# burnwire.net
KiCad netlist of a schematic drawn in Altium Designer
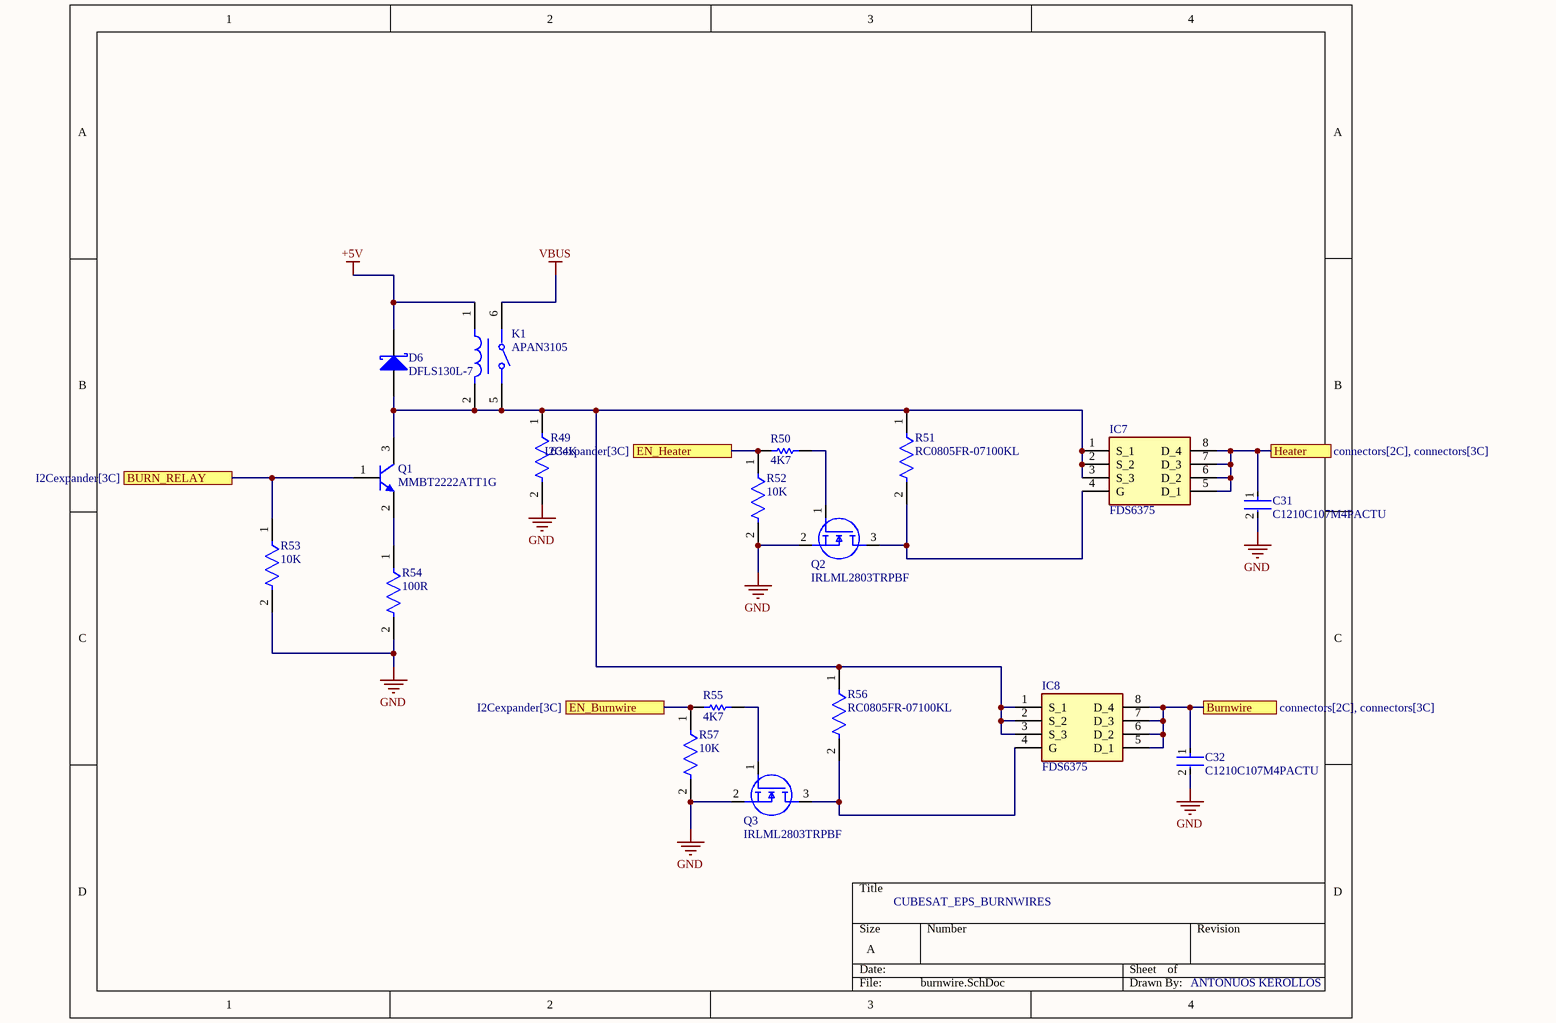
[diagram p0: burnwire.SchDoc]

(export (version "E")
  (design (tool "Eeschema 10.0.6"))
  (components
    (comp (ref "C31")
      (value "C1210C107M4PACTU")
      (footprint "FP-C1210C-FS-MFG")
      (description "CAP CER 100UF 16V X5R 1210")
      (fields (field (name "TOLERANCE") "20%"))
      (libsource (lib "Altium Content Vault") (part "02cd4be3c70576c341d710602a673aa"))
    )
    (comp (ref "C32")
      (value "C1210C107M4PACTU")
      (footprint "FP-C1210C-FS-MFG")
      (description "CAP CER 100UF 16V X5R 1210")
      (fields (field (name "TOLERANCE") "20%"))
      (libsource (lib "Altium Content Vault") (part "02cd4be3c70576c341d710602a673aa"))
    )
    (comp (ref "D6")
      (value "DFLS130L-7")
      (footprint "DIOD-POWERDI123-2_A_V")
      (description "Schottky Barrier Rectifier, 30 V, 1 A, -40 to 125 degC, 2-Pin SMD, RoHS, Tape and Reel")
      (fields (field (name "MANUFACTURER") "Diodes Inc"))
      (libsource (lib "Altium Content Vault") (part "DSKY-AK-2"))
    )
    (comp (ref "IC7")
      (value "FDS6375")
      (footprint "SamacSys:SOIC127P600X175-8N")
      (description "Integrated Circuit")
      (fields (field (name "MOUSER PART NUMBER") "512-FDS6375"))
      (libsource (lib "*") (part "FDS6375"))
    )
    (comp (ref "IC8")
      (value "FDS6375")
      (footprint "SamacSys:SOIC127P600X175-8N")
      (description "Integrated Circuit")
      (fields (field (name "MOUSER PART NUMBER") "512-FDS6375"))
      (libsource (lib "*") (part "FDS6375"))
    )
    (comp (ref "K1")
      (value "APAN3105")
      (footprint "FP-APAN3105-MFG")
      (description "RELAY GENERAL PURPOSE SPST 5A 5V")
      (libsource (lib "Altium Content Vault") (part "fce70d0d91a7d3418c43728939eaaf2"))
    )
    (comp (ref "Q1")
      (value "MMBT2222ATT1G")
      (footprint "ONSC-SC-75-3-463-01_V")
      (description "General Purpose Transistor, NPN Silicon, 3-Pin SC-75, Pb-Free, Tape and Reel")
      (fields (field (name "MANUFACTURER") "On Semiconductor"))
      (libsource (lib "Altium Content Vault") (part "ONSC-NPN-B1E2C3-3"))
    )
    (comp (ref "Q2")
      (value "IRLML2803TRPBF")
      (footprint "SamacSys:SOT95P237X112-3N")
      (description "MOSFET (N-Channel)")
      (fields (field (name "MOUSER PART NUMBER") "942-IRLML2803TRPBF"))
      (libsource (lib "*") (part "IRLML2803TRPBF"))
    )
    (comp (ref "Q3")
      (value "IRLML2803TRPBF")
      (footprint "SamacSys:SOT95P237X112-3N")
      (description "MOSFET (N-Channel)")
      (fields (field (name "MOUSER PART NUMBER") "942-IRLML2803TRPBF"))
      (libsource (lib "*") (part "IRLML2803TRPBF"))
    )
    (comp (ref "R49")
      (value "634K")
      (footprint "FP-CRCW0805-e3-IPC_A")
      (description "RES Thick Film, 634kΩ, 1%, 0.125W, 100ppm/°C, 0805")
      (fields (field (name "TOLERANCE") "1%"))
      (libsource (lib "Altium Content Vault") (part "1029c3af85768c4190bb7ad29bc67b5"))
    )
    (comp (ref "R50")
      (value "4K7")
      (footprint "YAGO-RC0805_M")
      (fields
        (field (name "TOLERANCE") "+/- 1%")
        (field (name "PARTNUMBER") "RC0805FR-074K7L")
        (field (name "POWER") "0.125 W")
      )
      (libsource (lib "Altium Content Vault") (part "YAGO-RES-2"))
    )
    (comp (ref "R51")
      (value "RC0805FR-07100KL")
      (footprint "FP-RC0805-0_6-IPC_C")
      (description "RES 100K OHM 1% 1/8W 0805")
      (fields (field (name "TOLERANCE") "1%"))
      (libsource (lib "Altium Content Vault") (part "1029c3af85768c4190bb7ad29bc67b5"))
    )
    (comp (ref "R52")
      (value "10K")
      (footprint "FP-CRCW0805-e3-IPC_A")
      (description "RES Thick Film, 10kΩ, 1%, 0.125W, 100ppm/°C, 0805")
      (fields (field (name "TOLERANCE") "1%"))
      (libsource (lib "Altium Content Vault") (part "1029c3af85768c4190bb7ad29bc67b5"))
    )
    (comp (ref "R53")
      (value "10K")
      (footprint "FP-CRCW0805-e3-IPC_A")
      (description "RES Thick Film, 10kΩ, 1%, 0.125W, 100ppm/°C, 0805")
      (fields (field (name "TOLERANCE") "1%"))
      (libsource (lib "Altium Content Vault") (part "1029c3af85768c4190bb7ad29bc67b5"))
    )
    (comp (ref "R54")
      (value "100R")
      (footprint "FP-RC0603-0_55-MFG")
      (fields (field (name "TOLERANCE") "1%"))
      (libsource (lib "Altium Content Vault") (part "1029c3af85768c4190bb7ad29bc67b5"))
    )
    (comp (ref "R55")
      (value "4K7")
      (footprint "YAGO-RC0805_M")
      (fields
        (field (name "TOLERANCE") "+/- 1%")
        (field (name "PARTNUMBER") "RC0805FR-074K7L")
        (field (name "POWER") "0.125 W")
      )
      (libsource (lib "Altium Content Vault") (part "YAGO-RES-2"))
    )
    (comp (ref "R56")
      (value "RC0805FR-07100KL")
      (footprint "FP-RC0805-0_6-IPC_C")
      (description "RES 100K OHM 1% 1/8W 0805")
      (fields (field (name "TOLERANCE") "1%"))
      (libsource (lib "Altium Content Vault") (part "1029c3af85768c4190bb7ad29bc67b5"))
    )
    (comp (ref "R57")
      (value "10K")
      (footprint "FP-CRCW0805-e3-IPC_A")
      (description "RES Thick Film, 10kΩ, 1%, 0.125W, 100ppm/°C, 0805")
      (fields (field (name "TOLERANCE") "1%"))
      (libsource (lib "Altium Content Vault") (part "1029c3af85768c4190bb7ad29bc67b5"))
    )
  )
  (nets
    (net (code "1") (name "+5V") (class "Default")
      (node (ref "D6") (pin "2") (pinfunction "K_2") (pintype "passive"))
      (node (ref "K1") (pin "1") (pinfunction "1_1") (pintype "passive"))
    )
    (net (code "2") (name "/BURN_RELAY") (class "Default")
      (node (ref "Q1") (pin "1") (pinfunction "B_1") (pintype "passive"))
      (node (ref "R53") (pin "1") (pinfunction "1_1") (pintype "passive"))
    )
    (net (code "3") (name "/Burnwire") (class "Default")
      (node (ref "C32") (pin "1") (pinfunction "1_1") (pintype "passive"))
      (node (ref "IC8") (pin "5") (pinfunction "D_1_5") (pintype "passive"))
      (node (ref "IC8") (pin "6") (pinfunction "D_2_6") (pintype "passive"))
      (node (ref "IC8") (pin "7") (pinfunction "D_3_7") (pintype "passive"))
      (node (ref "IC8") (pin "8") (pinfunction "D_4_8") (pintype "passive"))
    )
    (net (code "4") (name "/EN_Burnwire") (class "Default")
      (node (ref "R55") (pin "1") (pinfunction "1_1") (pintype "passive"))
      (node (ref "R57") (pin "1") (pinfunction "1_1") (pintype "passive"))
    )
    (net (code "5") (name "/EN_Heater") (class "Default")
      (node (ref "R50") (pin "1") (pinfunction "1_1") (pintype "passive"))
      (node (ref "R52") (pin "1") (pinfunction "1_1") (pintype "passive"))
    )
    (net (code "6") (name "/Heater") (class "Default")
      (node (ref "C31") (pin "1") (pinfunction "1_1") (pintype "passive"))
      (node (ref "IC7") (pin "5") (pinfunction "D_1_5") (pintype "passive"))
      (node (ref "IC7") (pin "6") (pinfunction "D_2_6") (pintype "passive"))
      (node (ref "IC7") (pin "7") (pinfunction "D_3_7") (pintype "passive"))
      (node (ref "IC7") (pin "8") (pinfunction "D_4_8") (pintype "passive"))
    )
    (net (code "7") (name "GND") (class "Default")
      (node (ref "C31") (pin "2") (pinfunction "2_2") (pintype "passive"))
      (node (ref "C32") (pin "2") (pinfunction "2_2") (pintype "passive"))
      (node (ref "Q2") (pin "2") (pinfunction "S_2") (pintype "passive"))
      (node (ref "Q3") (pin "2") (pinfunction "S_2") (pintype "passive"))
      (node (ref "R49") (pin "2") (pinfunction "2_2") (pintype "passive"))
      (node (ref "R52") (pin "2") (pinfunction "2_2") (pintype "passive"))
      (node (ref "R53") (pin "2") (pinfunction "2_2") (pintype "passive"))
      (node (ref "R54") (pin "2") (pinfunction "2_2") (pintype "passive"))
      (node (ref "R57") (pin "2") (pinfunction "2_2") (pintype "passive"))
    )
    (net (code "8") (name "Net-(D6-A)") (class "Default")
      (node (ref "D6") (pin "1") (pinfunction "A_1") (pintype "passive"))
      (node (ref "IC7") (pin "1") (pinfunction "S_1_1") (pintype "passive"))
      (node (ref "IC7") (pin "2") (pinfunction "S_2_2") (pintype "passive"))
      (node (ref "IC7") (pin "3") (pinfunction "S_3_3") (pintype "passive"))
      (node (ref "IC8") (pin "1") (pinfunction "S_1_1") (pintype "passive"))
      (node (ref "IC8") (pin "2") (pinfunction "S_2_2") (pintype "passive"))
      (node (ref "IC8") (pin "3") (pinfunction "S_3_3") (pintype "passive"))
      (node (ref "K1") (pin "2") (pinfunction "2_2") (pintype "passive"))
      (node (ref "K1") (pin "5") (pinfunction "NO_5") (pintype "passive"))
      (node (ref "Q1") (pin "3") (pinfunction "C_3") (pintype "passive"))
      (node (ref "R49") (pin "1") (pinfunction "1_1") (pintype "passive"))
      (node (ref "R51") (pin "1") (pinfunction "1_1") (pintype "passive"))
      (node (ref "R56") (pin "1") (pinfunction "1_1") (pintype "passive"))
    )
    (net (code "9") (name "Net-(IC7-G)") (class "Default")
      (node (ref "IC7") (pin "4") (pinfunction "G_4") (pintype "passive"))
      (node (ref "Q2") (pin "3") (pinfunction "D_3") (pintype "passive"))
      (node (ref "R51") (pin "2") (pinfunction "2_2") (pintype "passive"))
    )
    (net (code "10") (name "Net-(IC8-G)") (class "Default")
      (node (ref "IC8") (pin "4") (pinfunction "G_4") (pintype "passive"))
      (node (ref "Q3") (pin "3") (pinfunction "D_3") (pintype "passive"))
      (node (ref "R56") (pin "2") (pinfunction "2_2") (pintype "passive"))
    )
    (net (code "11") (name "Net-(Q1-E)") (class "Default")
      (node (ref "Q1") (pin "2") (pinfunction "E_2") (pintype "passive"))
      (node (ref "R54") (pin "1") (pinfunction "1_1") (pintype "passive"))
    )
    (net (code "12") (name "Net-(Q2-G)") (class "Default")
      (node (ref "Q2") (pin "1") (pinfunction "G_1") (pintype "passive"))
      (node (ref "R50") (pin "2") (pinfunction "2_2") (pintype "passive"))
    )
    (net (code "13") (name "Net-(Q3-G)") (class "Default")
      (node (ref "Q3") (pin "1") (pinfunction "G_1") (pintype "passive"))
      (node (ref "R55") (pin "2") (pinfunction "2_2") (pintype "passive"))
    )
    (net (code "14") (name "VBUS") (class "Default")
      (node (ref "K1") (pin "6") (pinfunction "COM_6") (pintype "passive"))
    )
  )
)
